# mapleCUx_large_310.net
KiCad netlist of a schematic drawn in EAGLE
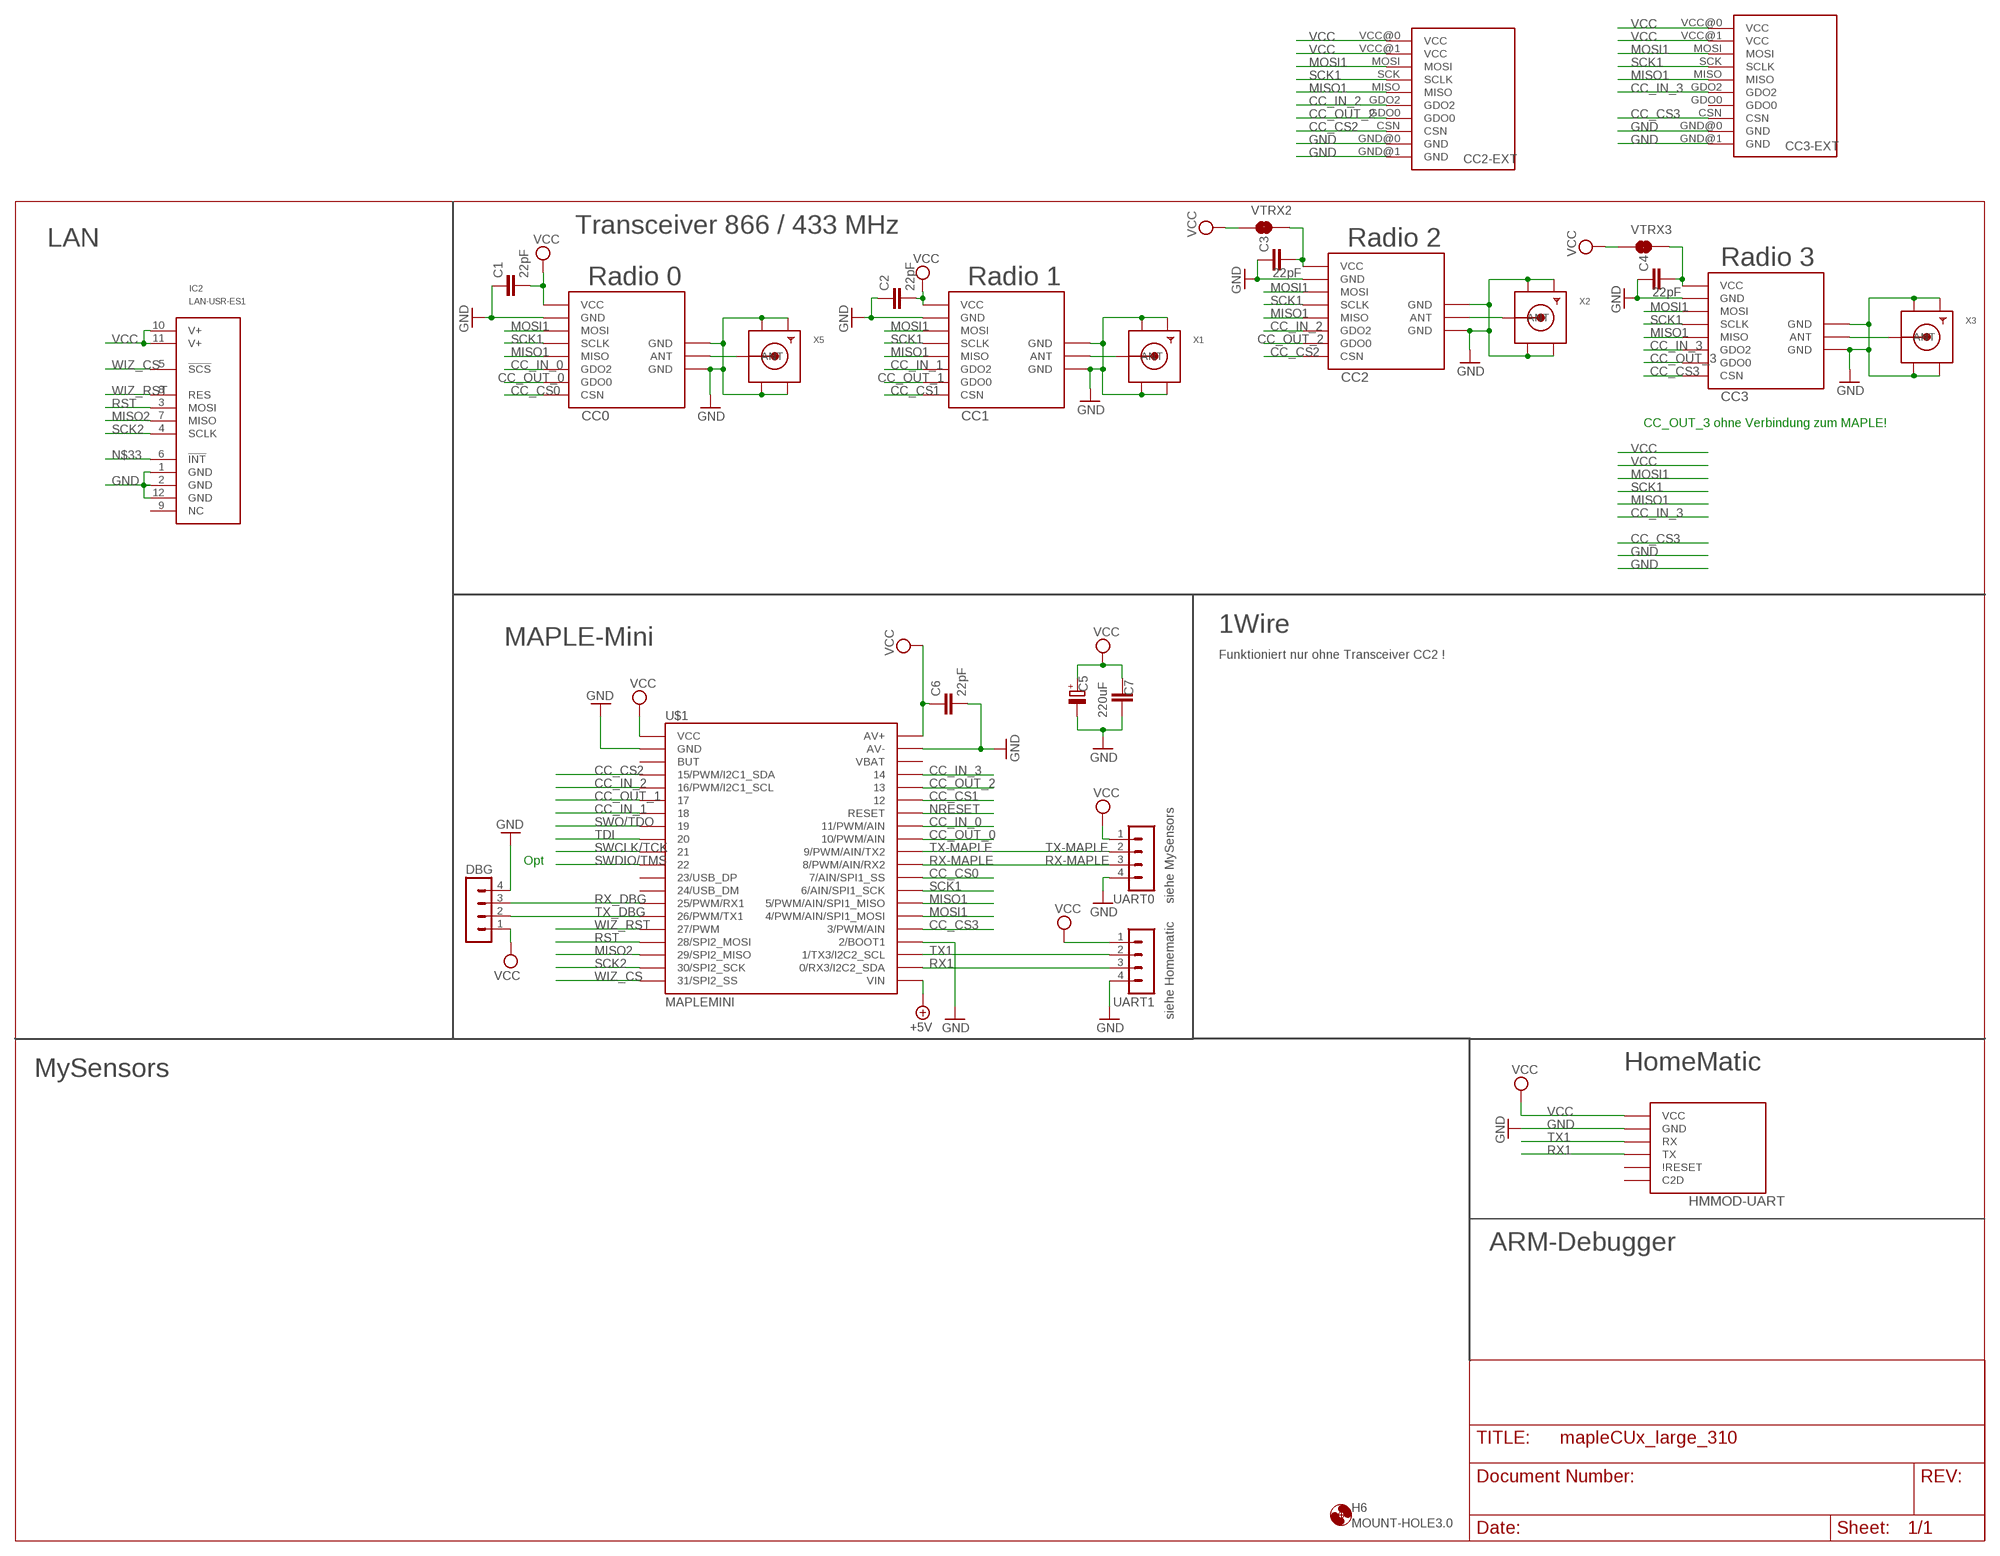
[diagram p0: schematic, sheet 1]

(export (version "E")
  (design (tool "Eeschema 10.0.6"))
  (components
    (comp (ref "C1")
      (value "22pF")
      (footprint "eagle-import:C0805")
      (libsource (lib "eagle-import") (part "C-EUC0805"))
    )
    (comp (ref "C2")
      (value "22pF")
      (footprint "eagle-import:C0805")
      (libsource (lib "eagle-import") (part "C-EUC0805"))
    )
    (comp (ref "C3")
      (value "22pF")
      (footprint "eagle-import:C0805")
      (libsource (lib "eagle-import") (part "C-EUC0805"))
    )
    (comp (ref "C4")
      (value "22pF")
      (footprint "eagle-import:C0805")
      (libsource (lib "eagle-import") (part "C-EUC0805"))
    )
    (comp (ref "C5")
      (value "220uF")
      (footprint "eagle-import:E5-8,5")
      (libsource (lib "eagle-import") (part "CPOL-EUE5-8.5"))
    )
    (comp (ref "C6")
      (value "22pF")
      (footprint "eagle-import:C0805")
      (libsource (lib "eagle-import") (part "C-EUC0805"))
    )
    (comp (ref "C7")
      (value "C-EUC1812")
      (footprint "eagle-import:C1812")
      (libsource (lib "eagle-import") (part "C-EUC1812"))
    )
    (comp (ref "CC0")
      (value "CC1101")
      (footprint "eagle-import:CC1101_MODULE1_SMD")
      (libsource (lib "eagle-import") (part "CC1101_MODULE1SMD"))
    )
    (comp (ref "CC1")
      (value "CC1101_MODULE1SMD")
      (footprint "eagle-import:CC1101_MODULE1_SMD")
      (libsource (lib "eagle-import") (part "CC1101_MODULE1SMD"))
    )
    (comp (ref "CC2")
      (value "CC1101_MODULE1SMD")
      (footprint "eagle-import:CC1101_MODULE1_SMD")
      (libsource (lib "eagle-import") (part "CC1101_MODULE1SMD"))
    )
    (comp (ref "CC2-EXT")
      (value "CC1101_MODULE3_DIL")
      (footprint "eagle-import:CC1101_MODULE3_DIL")
      (libsource (lib "eagle-import") (part "CC1101_MODULE3_DIL"))
    )
    (comp (ref "CC3")
      (value "CC1101_MODULE1SMD")
      (footprint "eagle-import:CC1101_MODULE1_SMD")
      (libsource (lib "eagle-import") (part "CC1101_MODULE1SMD"))
    )
    (comp (ref "CC3-EXT")
      (value "CC1101_MODULE3_DIL")
      (footprint "eagle-import:CC1101_MODULE3_DIL")
      (libsource (lib "eagle-import") (part "CC1101_MODULE3_DIL"))
    )
    (comp (ref "DBG")
      (value "MA04-1")
      (footprint "eagle-import:MA04-1")
      (libsource (lib "eagle-import") (part "MA04-1"))
    )
    (comp (ref "H6")
      (value "MOUNT-HOLE3.0")
      (footprint "eagle-import:3,0")
      (libsource (lib "eagle-import") (part "MOUNT-HOLE3.0"))
    )
    (comp (ref "HMMOD-UART")
      (value "HM-MOD-UARTDIL")
      (footprint "eagle-import:HM-MOD-UART-DIL")
      (libsource (lib "eagle-import") (part "HM-MOD-UARTDIL"))
    )
    (comp (ref "IC2")
      (value "LAN-USR-ES1")
      (footprint "eagle-import:USR-ES1")
      (libsource (lib "eagle-import") (part "LAN-USR-ES1"))
    )
    (comp (ref "U$1")
      (value "MAPLEMINI")
      (footprint "eagle-import:20-DIP")
      (libsource (lib "eagle-import") (part "MAPLEMINI"))
    )
    (comp (ref "UART0")
      (value "MA04-1")
      (footprint "eagle-import:MA04-1")
      (libsource (lib "eagle-import") (part "MA04-1"))
    )
    (comp (ref "UART1")
      (value "MA04-1")
      (footprint "eagle-import:MA04-1")
      (libsource (lib "eagle-import") (part "MA04-1"))
    )
    (comp (ref "VTRX2")
      (value "JUMPER-SMT_2_NC_TRACE_SILK")
      (footprint "eagle-import:SMT-JUMPER_2_NC_TRACE_SILK")
      (libsource (lib "eagle-import") (part "JUMPER-SMT_2_NC_TRACE_SILK"))
    )
    (comp (ref "VTRX3")
      (value "JUMPER-SMT_2_NC_TRACE_SILK")
      (footprint "eagle-import:SMT-JUMPER_2_NC_TRACE_SILK")
      (libsource (lib "eagle-import") (part "JUMPER-SMT_2_NC_TRACE_SILK"))
    )
    (comp (ref "X1")
      (value "SMACONNECTOR_EDGE")
      (footprint "eagle-import:SMA_EDGELAUNCH")
      (libsource (lib "eagle-import") (part "SMACONNECTOR_EDGE"))
    )
    (comp (ref "X2")
      (value "SMACONNECTOR_EDGE")
      (footprint "eagle-import:SMA_EDGELAUNCH")
      (libsource (lib "eagle-import") (part "SMACONNECTOR_EDGE"))
    )
    (comp (ref "X3")
      (value "SMACONNECTOR_EDGE")
      (footprint "eagle-import:SMA_EDGELAUNCH")
      (libsource (lib "eagle-import") (part "SMACONNECTOR_EDGE"))
    )
    (comp (ref "X5")
      (value "SMACONNECTOR_EDGE")
      (footprint "eagle-import:SMA_EDGELAUNCH")
      (libsource (lib "eagle-import") (part "SMACONNECTOR_EDGE"))
    )
  )
  (nets
    (net (code "1") (name "+5V") (class "Default")
      (node (ref "U$1") (pin "21") (pinfunction "VIN_21") (pintype "bidirectional"))
    )
    (net (code "2") (name "/CC_CS0") (class "Default")
      (node (ref "CC0") (pin "CSN") (pinfunction "CSN_CSN") (pintype "bidirectional"))
      (node (ref "U$1") (pin "29") (pinfunction "7/AIN/SPI1_SS_29") (pintype "bidirectional"))
    )
    (net (code "3") (name "/CC_CS1") (class "Default")
      (node (ref "CC1") (pin "CSN") (pinfunction "CSN_CSN") (pintype "bidirectional"))
      (node (ref "U$1") (pin "35") (pinfunction "12_35") (pintype "bidirectional"))
    )
    (net (code "4") (name "/CC_CS2") (class "Default")
      (node (ref "CC2") (pin "CSN") (pinfunction "CSN_CSN") (pintype "bidirectional"))
      (node (ref "CC2-EXT") (pin "CSN") (pinfunction "CSN_CSN") (pintype "bidirectional"))
      (node (ref "U$1") (pin "4") (pinfunction "15/PWM/I2C1_SDA_4") (pintype "bidirectional"))
    )
    (net (code "5") (name "/CC_CS3") (class "Default")
      (node (ref "CC3") (pin "CSN") (pinfunction "CSN_CSN") (pintype "bidirectional"))
      (node (ref "CC3-EXT") (pin "CSN") (pinfunction "CSN_CSN") (pintype "bidirectional"))
      (node (ref "U$1") (pin "25") (pinfunction "3/PWM/AIN_25") (pintype "bidirectional"))
    )
    (net (code "6") (name "/CC_IN_0") (class "Default")
      (node (ref "CC0") (pin "GDO2") (pinfunction "GDO2_GDO2") (pintype "bidirectional"))
      (node (ref "U$1") (pin "33") (pinfunction "11/PWM/AIN_33") (pintype "bidirectional"))
    )
    (net (code "7") (name "/CC_IN_1") (class "Default")
      (node (ref "CC1") (pin "GDO2") (pinfunction "GDO2_GDO2") (pintype "bidirectional"))
      (node (ref "U$1") (pin "7") (pinfunction "18_7") (pintype "bidirectional"))
    )
    (net (code "8") (name "/CC_IN_2") (class "Default")
      (node (ref "CC2") (pin "GDO2") (pinfunction "GDO2_GDO2") (pintype "bidirectional"))
      (node (ref "CC2-EXT") (pin "GDO2") (pinfunction "GDO2_GDO2") (pintype "bidirectional"))
      (node (ref "U$1") (pin "5") (pinfunction "16/PWM/I2C1_SCL_5") (pintype "bidirectional"))
    )
    (net (code "9") (name "/CC_IN_3") (class "Default")
      (node (ref "CC3") (pin "GDO2") (pinfunction "GDO2_GDO2") (pintype "bidirectional"))
      (node (ref "CC3-EXT") (pin "GDO2") (pinfunction "GDO2_GDO2") (pintype "bidirectional"))
      (node (ref "U$1") (pin "37") (pinfunction "14_37") (pintype "bidirectional"))
    )
    (net (code "10") (name "/CC_OUT_0") (class "Default")
      (node (ref "CC0") (pin "GDO0") (pinfunction "GDO0_GDO0") (pintype "bidirectional"))
      (node (ref "U$1") (pin "32") (pinfunction "10/PWM/AIN_32") (pintype "bidirectional"))
    )
    (net (code "11") (name "/CC_OUT_1") (class "Default")
      (node (ref "CC1") (pin "GDO0") (pinfunction "GDO0_GDO0") (pintype "bidirectional"))
      (node (ref "U$1") (pin "6") (pinfunction "17_6") (pintype "bidirectional"))
    )
    (net (code "12") (name "/CC_OUT_2") (class "Default")
      (node (ref "CC2") (pin "GDO0") (pinfunction "GDO0_GDO0") (pintype "bidirectional"))
      (node (ref "CC2-EXT") (pin "GDO0") (pinfunction "GDO0_GDO0") (pintype "bidirectional"))
      (node (ref "U$1") (pin "36") (pinfunction "13_36") (pintype "bidirectional"))
    )
    (net (code "13") (name "/CC_OUT_3") (class "Default")
      (node (ref "CC3") (pin "GDO0") (pinfunction "GDO0_GDO0") (pintype "bidirectional"))
    )
    (net (code "14") (name "/MISO1") (class "Default")
      (node (ref "CC0") (pin "MISO") (pinfunction "MISO_MISO") (pintype "bidirectional"))
      (node (ref "CC1") (pin "MISO") (pinfunction "MISO_MISO") (pintype "bidirectional"))
      (node (ref "CC2") (pin "MISO") (pinfunction "MISO_MISO") (pintype "bidirectional"))
      (node (ref "CC2-EXT") (pin "MISO") (pinfunction "MISO_MISO") (pintype "bidirectional"))
      (node (ref "CC3") (pin "MISO") (pinfunction "MISO_MISO") (pintype "bidirectional"))
      (node (ref "CC3-EXT") (pin "MISO") (pinfunction "MISO_MISO") (pintype "bidirectional"))
      (node (ref "U$1") (pin "27") (pinfunction "5/PWM/AIN/SPI1_MISO_27") (pintype "bidirectional"))
    )
    (net (code "15") (name "/MISO2") (class "Default")
      (node (ref "IC2") (pin "7") (pinfunction "MISO_7") (pintype "bidirectional"))
      (node (ref "U$1") (pin "18") (pinfunction "29/SPI2_MISO_18") (pintype "bidirectional"))
    )
    (net (code "16") (name "/MOSI1") (class "Default")
      (node (ref "CC0") (pin "MOSI") (pinfunction "MOSI_MOSI") (pintype "bidirectional"))
      (node (ref "CC1") (pin "MOSI") (pinfunction "MOSI_MOSI") (pintype "bidirectional"))
      (node (ref "CC2") (pin "MOSI") (pinfunction "MOSI_MOSI") (pintype "bidirectional"))
      (node (ref "CC2-EXT") (pin "MOSI") (pinfunction "MOSI_MOSI") (pintype "bidirectional"))
      (node (ref "CC3") (pin "MOSI") (pinfunction "MOSI_MOSI") (pintype "bidirectional"))
      (node (ref "CC3-EXT") (pin "MOSI") (pinfunction "MOSI_MOSI") (pintype "bidirectional"))
      (node (ref "U$1") (pin "26") (pinfunction "4/PWM/AIN/SPI1_MOSI_26") (pintype "bidirectional"))
    )
    (net (code "17") (name "/N$33") (class "Default")
      (node (ref "IC2") (pin "6") (pinfunction "~{INT}_6") (pintype "output"))
    )
    (net (code "18") (name "/NRESET") (class "Default")
      (node (ref "U$1") (pin "34") (pinfunction "RESET_34") (pintype "bidirectional"))
    )
    (net (code "19") (name "/RST") (class "Default")
      (node (ref "IC2") (pin "3") (pinfunction "MOSI_3") (pintype "bidirectional"))
      (node (ref "U$1") (pin "17") (pinfunction "28/SPI2_MOSI_17") (pintype "bidirectional"))
    )
    (net (code "20") (name "/RX-MAPLE") (class "Default")
      (node (ref "U$1") (pin "30") (pinfunction "8/PWM/AIN/RX2_30") (pintype "bidirectional"))
      (node (ref "UART0") (pin "3") (pinfunction "3_3") (pintype "passive"))
    )
    (net (code "21") (name "/RX1") (class "Default")
      (node (ref "HMMOD-UART") (pin "5") (pinfunction "TX_5") (pintype "bidirectional"))
      (node (ref "U$1") (pin "22") (pinfunction "0/RX3/I2C2_SDA_22") (pintype "bidirectional"))
      (node (ref "UART1") (pin "3") (pinfunction "3_3") (pintype "passive"))
    )
    (net (code "22") (name "/RX_DBG") (class "Default")
      (node (ref "DBG") (pin "3") (pinfunction "3_3") (pintype "passive"))
      (node (ref "U$1") (pin "14") (pinfunction "25/PWM/RX1_14") (pintype "bidirectional"))
    )
    (net (code "23") (name "/SCK1") (class "Default")
      (node (ref "CC0") (pin "SCLK") (pinfunction "SCLK_SCLK") (pintype "bidirectional"))
      (node (ref "CC1") (pin "SCLK") (pinfunction "SCLK_SCLK") (pintype "bidirectional"))
      (node (ref "CC2") (pin "SCLK") (pinfunction "SCLK_SCLK") (pintype "bidirectional"))
      (node (ref "CC2-EXT") (pin "SCK") (pinfunction "SCLK_SCK") (pintype "bidirectional"))
      (node (ref "CC3") (pin "SCLK") (pinfunction "SCLK_SCLK") (pintype "bidirectional"))
      (node (ref "CC3-EXT") (pin "SCK") (pinfunction "SCLK_SCK") (pintype "bidirectional"))
      (node (ref "U$1") (pin "28") (pinfunction "6/AIN/SPI1_SCK_28") (pintype "bidirectional"))
    )
    (net (code "24") (name "/SCK2") (class "Default")
      (node (ref "IC2") (pin "4") (pinfunction "SCLK_4") (pintype "input"))
      (node (ref "U$1") (pin "19") (pinfunction "30/SPI2_SCK_19") (pintype "bidirectional"))
    )
    (net (code "25") (name "/SWCLK{slash}TCK") (class "Default")
      (node (ref "U$1") (pin "10") (pinfunction "21_10") (pintype "bidirectional"))
    )
    (net (code "26") (name "/SWDIO{slash}TMS") (class "Default")
      (node (ref "U$1") (pin "11") (pinfunction "22_11") (pintype "bidirectional"))
    )
    (net (code "27") (name "/SWO{slash}TDO") (class "Default")
      (node (ref "U$1") (pin "8") (pinfunction "19_8") (pintype "bidirectional"))
    )
    (net (code "28") (name "/TDI") (class "Default")
      (node (ref "U$1") (pin "9") (pinfunction "20_9") (pintype "bidirectional"))
    )
    (net (code "29") (name "/TX-MAPLE") (class "Default")
      (node (ref "U$1") (pin "31") (pinfunction "9/PWM/AIN/TX2_31") (pintype "bidirectional"))
      (node (ref "UART0") (pin "2") (pinfunction "2_2") (pintype "passive"))
    )
    (net (code "30") (name "/TX1") (class "Default")
      (node (ref "HMMOD-UART") (pin "6") (pinfunction "RX_6") (pintype "bidirectional"))
      (node (ref "U$1") (pin "23") (pinfunction "1/TX3/I2C2_SCL_23") (pintype "bidirectional"))
      (node (ref "UART1") (pin "2") (pinfunction "2_2") (pintype "passive"))
    )
    (net (code "31") (name "/TX_DBG") (class "Default")
      (node (ref "DBG") (pin "2") (pinfunction "2_2") (pintype "passive"))
      (node (ref "U$1") (pin "15") (pinfunction "26/PWM/TX1_15") (pintype "bidirectional"))
    )
    (net (code "32") (name "/WIZ_CS") (class "Default")
      (node (ref "IC2") (pin "5") (pinfunction "~{SCS}_5") (pintype "input"))
      (node (ref "U$1") (pin "20") (pinfunction "31/SPI2_SS_20") (pintype "bidirectional"))
    )
    (net (code "33") (name "/WIZ_RST") (class "Default")
      (node (ref "IC2") (pin "8") (pinfunction "RES_8") (pintype "input"))
      (node (ref "U$1") (pin "16") (pinfunction "27/PWM_16") (pintype "bidirectional"))
    )
    (net (code "34") (name "GND") (class "Default")
      (node (ref "C1") (pin "1") (pinfunction "1_1") (pintype "passive"))
      (node (ref "C2") (pin "1") (pinfunction "1_1") (pintype "passive"))
      (node (ref "C3") (pin "1") (pinfunction "1_1") (pintype "passive"))
      (node (ref "C4") (pin "1") (pinfunction "1_1") (pintype "passive"))
      (node (ref "C5") (pin "-") (pinfunction "-_-") (pintype "passive"))
      (node (ref "C6") (pin "2") (pinfunction "2_2") (pintype "passive"))
      (node (ref "C7") (pin "1") (pinfunction "1_1") (pintype "passive"))
      (node (ref "CC0") (pin "GND@0") (pinfunction "GND_GND@0") (pintype "power_in"))
      (node (ref "CC0") (pin "GND@1") (pinfunction "GND_GND@1") (pintype "power_in"))
      (node (ref "CC0") (pin "GND@2") (pinfunction "GND_GND@2") (pintype "power_in"))
      (node (ref "CC1") (pin "GND@0") (pinfunction "GND_GND@0") (pintype "power_in"))
      (node (ref "CC1") (pin "GND@1") (pinfunction "GND_GND@1") (pintype "power_in"))
      (node (ref "CC1") (pin "GND@2") (pinfunction "GND_GND@2") (pintype "power_in"))
      (node (ref "CC2") (pin "GND@0") (pinfunction "GND_GND@0") (pintype "power_in"))
      (node (ref "CC2") (pin "GND@1") (pinfunction "GND_GND@1") (pintype "power_in"))
      (node (ref "CC2") (pin "GND@2") (pinfunction "GND_GND@2") (pintype "power_in"))
      (node (ref "CC2-EXT") (pin "GND@0") (pinfunction "GND_GND@0") (pintype "power_in"))
      (node (ref "CC2-EXT") (pin "GND@1") (pinfunction "GND_GND@1") (pintype "power_in"))
      (node (ref "CC3") (pin "GND@0") (pinfunction "GND_GND@0") (pintype "power_in"))
      (node (ref "CC3") (pin "GND@1") (pinfunction "GND_GND@1") (pintype "power_in"))
      (node (ref "CC3") (pin "GND@2") (pinfunction "GND_GND@2") (pintype "power_in"))
      (node (ref "CC3-EXT") (pin "GND@0") (pinfunction "GND_GND@0") (pintype "power_in"))
      (node (ref "CC3-EXT") (pin "GND@1") (pinfunction "GND_GND@1") (pintype "power_in"))
      (node (ref "DBG") (pin "4") (pinfunction "4_4") (pintype "passive"))
      (node (ref "HMMOD-UART") (pin "2") (pinfunction "GND_2") (pintype "power_in"))
      (node (ref "IC2") (pin "1") (pinfunction "GND_1") (pintype "power_in"))
      (node (ref "IC2") (pin "12") (pinfunction "GND_12") (pintype "power_in"))
      (node (ref "IC2") (pin "2") (pinfunction "GND_2") (pintype "power_in"))
      (node (ref "U$1") (pin "2") (pinfunction "GND_2") (pintype "bidirectional"))
      (node (ref "U$1") (pin "24") (pinfunction "2/BOOT1_24") (pintype "bidirectional"))
      (node (ref "U$1") (pin "39") (pinfunction "AV-_39") (pintype "bidirectional"))
      (node (ref "UART0") (pin "4") (pinfunction "4_4") (pintype "passive"))
      (node (ref "UART1") (pin "4") (pinfunction "4_4") (pintype "passive"))
      (node (ref "X1") (pin "GND@1") (pinfunction "GND4_GND@1") (pintype "power_in"))
      (node (ref "X1") (pin "GND@2") (pinfunction "GND3_GND@2") (pintype "power_in"))
      (node (ref "X1") (pin "GND@3") (pinfunction "GND2_GND@3") (pintype "power_in"))
      (node (ref "X1") (pin "GND@4") (pinfunction "GND1_GND@4") (pintype "power_in"))
      (node (ref "X2") (pin "GND@1") (pinfunction "GND4_GND@1") (pintype "power_in"))
      (node (ref "X2") (pin "GND@2") (pinfunction "GND3_GND@2") (pintype "power_in"))
      (node (ref "X2") (pin "GND@3") (pinfunction "GND2_GND@3") (pintype "power_in"))
      (node (ref "X2") (pin "GND@4") (pinfunction "GND1_GND@4") (pintype "power_in"))
      (node (ref "X3") (pin "GND@1") (pinfunction "GND4_GND@1") (pintype "power_in"))
      (node (ref "X3") (pin "GND@2") (pinfunction "GND3_GND@2") (pintype "power_in"))
      (node (ref "X3") (pin "GND@3") (pinfunction "GND2_GND@3") (pintype "power_in"))
      (node (ref "X3") (pin "GND@4") (pinfunction "GND1_GND@4") (pintype "power_in"))
      (node (ref "X5") (pin "GND@1") (pinfunction "GND4_GND@1") (pintype "power_in"))
      (node (ref "X5") (pin "GND@2") (pinfunction "GND3_GND@2") (pintype "power_in"))
      (node (ref "X5") (pin "GND@3") (pinfunction "GND2_GND@3") (pintype "power_in"))
      (node (ref "X5") (pin "GND@4") (pinfunction "GND1_GND@4") (pintype "power_in"))
    )
    (net (code "35") (name "Net-(C3-Pad2)") (class "Default")
      (node (ref "C3") (pin "2") (pinfunction "2_2") (pintype "passive"))
      (node (ref "CC2") (pin "VCC") (pinfunction "VCC_VCC") (pintype "power_in"))
      (node (ref "VTRX2") (pin "2") (pinfunction "2_2") (pintype "passive"))
    )
    (net (code "36") (name "Net-(C4-Pad2)") (class "Default")
      (node (ref "C4") (pin "2") (pinfunction "2_2") (pintype "passive"))
      (node (ref "CC3") (pin "VCC") (pinfunction "VCC_VCC") (pintype "power_in"))
      (node (ref "VTRX3") (pin "2") (pinfunction "2_2") (pintype "passive"))
    )
    (net (code "37") (name "Net-(X1-ANT)") (class "Default")
      (node (ref "CC1") (pin "ANT") (pinfunction "ANT_ANT") (pintype "output"))
      (node (ref "X1") (pin "P") (pinfunction "ANT_P") (pintype "bidirectional"))
    )
    (net (code "38") (name "Net-(X2-ANT)") (class "Default")
      (node (ref "CC2") (pin "ANT") (pinfunction "ANT_ANT") (pintype "output"))
      (node (ref "X2") (pin "P") (pinfunction "ANT_P") (pintype "bidirectional"))
    )
    (net (code "39") (name "Net-(X3-ANT)") (class "Default")
      (node (ref "CC3") (pin "ANT") (pinfunction "ANT_ANT") (pintype "output"))
      (node (ref "X3") (pin "P") (pinfunction "ANT_P") (pintype "bidirectional"))
    )
    (net (code "40") (name "Net-(X5-ANT)") (class "Default")
      (node (ref "CC0") (pin "ANT") (pinfunction "ANT_ANT") (pintype "output"))
      (node (ref "X5") (pin "P") (pinfunction "ANT_P") (pintype "bidirectional"))
    )
    (net (code "41") (name "VCC") (class "Default")
      (node (ref "C1") (pin "2") (pinfunction "2_2") (pintype "passive"))
      (node (ref "C2") (pin "2") (pinfunction "2_2") (pintype "passive"))
      (node (ref "C5") (pin "+") (pinfunction "+_+") (pintype "passive"))
      (node (ref "C6") (pin "1") (pinfunction "1_1") (pintype "passive"))
      (node (ref "C7") (pin "2") (pinfunction "2_2") (pintype "passive"))
      (node (ref "CC0") (pin "VCC") (pinfunction "VCC_VCC") (pintype "power_in"))
      (node (ref "CC1") (pin "VCC") (pinfunction "VCC_VCC") (pintype "power_in"))
      (node (ref "CC2-EXT") (pin "VCC@0") (pinfunction "VCC_VCC@0") (pintype "power_in"))
      (node (ref "CC2-EXT") (pin "VCC@1") (pinfunction "VCC_VCC@1") (pintype "power_in"))
      (node (ref "CC3-EXT") (pin "VCC@0") (pinfunction "VCC_VCC@0") (pintype "power_in"))
      (node (ref "CC3-EXT") (pin "VCC@1") (pinfunction "VCC_VCC@1") (pintype "power_in"))
      (node (ref "DBG") (pin "1") (pinfunction "1_1") (pintype "passive"))
      (node (ref "HMMOD-UART") (pin "1") (pinfunction "VCC_1") (pintype "power_in"))
      (node (ref "IC2") (pin "10") (pinfunction "V+_10") (pintype "power_in"))
      (node (ref "IC2") (pin "11") (pinfunction "V+_11") (pintype "power_in"))
      (node (ref "U$1") (pin "1") (pinfunction "VCC_1") (pintype "bidirectional"))
      (node (ref "U$1") (pin "40") (pinfunction "AV+_40") (pintype "bidirectional"))
      (node (ref "UART0") (pin "1") (pinfunction "1_1") (pintype "passive"))
      (node (ref "UART1") (pin "1") (pinfunction "1_1") (pintype "passive"))
      (node (ref "VTRX2") (pin "1") (pinfunction "1_1") (pintype "passive"))
      (node (ref "VTRX3") (pin "1") (pinfunction "1_1") (pintype "passive"))
    )
    (net (code "42") (name "unconnected-(CC3-EXT-PadGDO0)") (class "Default")
      (node (ref "CC3-EXT") (pin "GDO0") (pinfunction "GDO0_GDO0") (pintype "bidirectional"))
    )
    (net (code "43") (name "unconnected-(HMMOD-UART-C2D-Pad3)") (class "Default")
      (node (ref "HMMOD-UART") (pin "3") (pinfunction "C2D_3") (pintype "bidirectional"))
    )
    (net (code "44") (name "unconnected-(HMMOD-UART-\\~{RESET}-Pad4)") (class "Default")
      (node (ref "HMMOD-UART") (pin "4") (pinfunction "\\~{RESET}_4") (pintype "bidirectional"))
    )
    (net (code "45") (name "unconnected-(IC2-NC-Pad9)") (class "Default")
      (node (ref "IC2") (pin "9") (pinfunction "NC_9") (pintype "no_connect"))
    )
    (net (code "46") (name "unconnected-(U$1-23{slash}USB_DP-Pad12)") (class "Default")
      (node (ref "U$1") (pin "12") (pinfunction "23/USB_DP_12") (pintype "bidirectional"))
    )
    (net (code "47") (name "unconnected-(U$1-24{slash}USB_DM-Pad13)") (class "Default")
      (node (ref "U$1") (pin "13") (pinfunction "24/USB_DM_13") (pintype "bidirectional"))
    )
    (net (code "48") (name "unconnected-(U$1-BUT-Pad3)") (class "Default")
      (node (ref "U$1") (pin "3") (pinfunction "BUT_3") (pintype "bidirectional"))
    )
    (net (code "49") (name "unconnected-(U$1-VBAT-Pad38)") (class "Default")
      (node (ref "U$1") (pin "38") (pinfunction "VBAT_38") (pintype "bidirectional"))
    )
  )
)
